# MainSw.net
KiCad netlist of a schematic drawn in Altium Designer
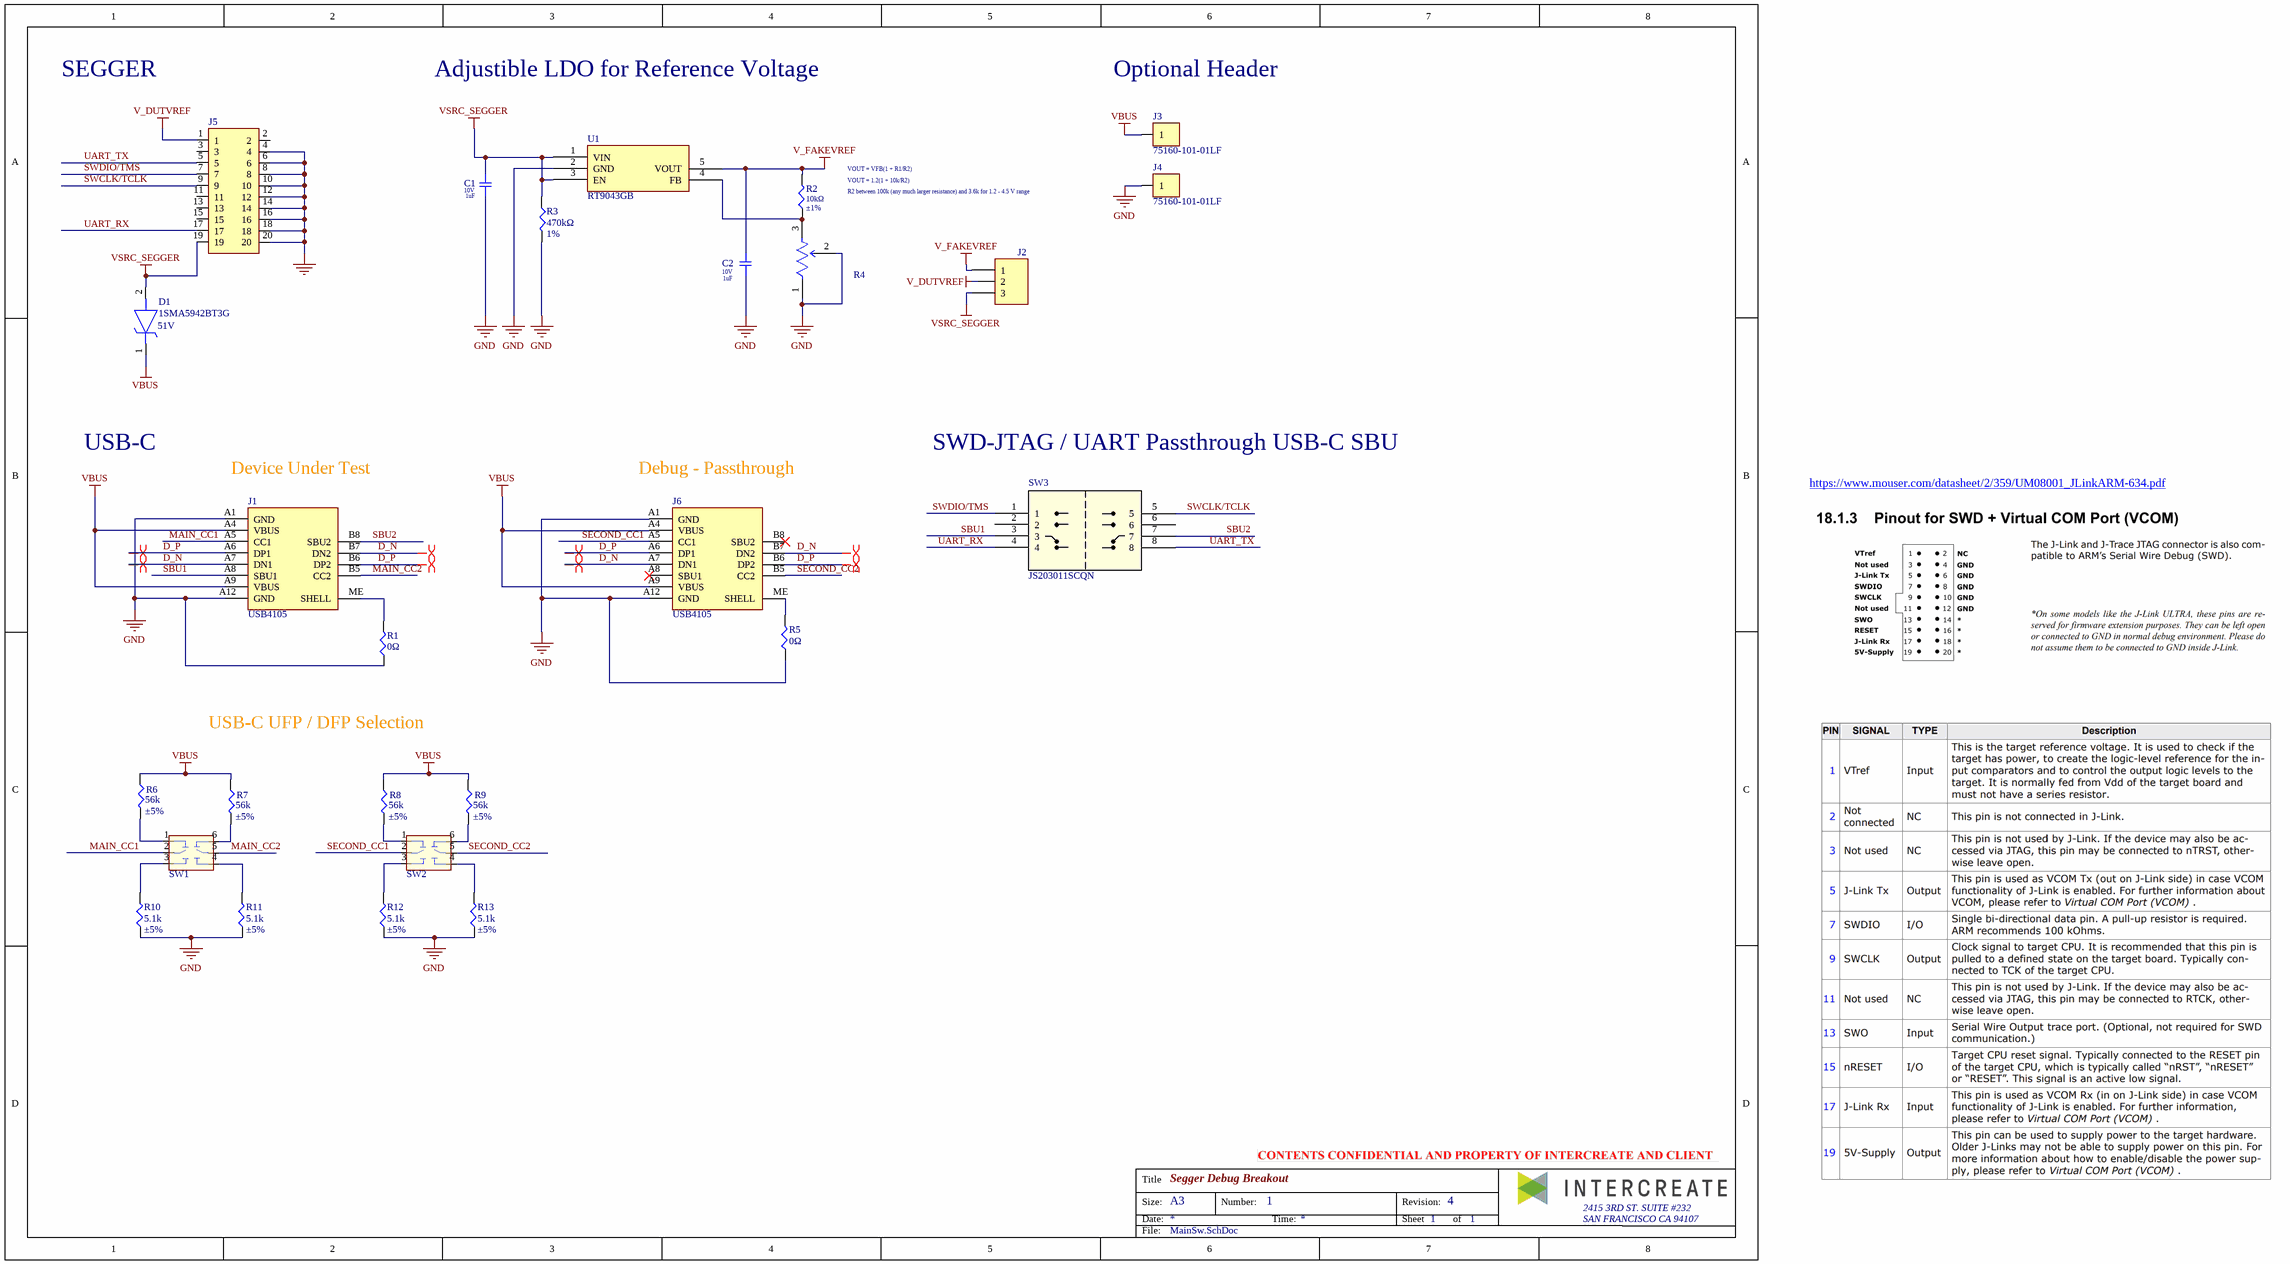
[diagram p0: MainSw.SchDoc]

(export (version "E")
  (design (tool "Eeschema 10.0.6"))
  (components
    (comp (ref "C1")
      (value "0402ZD105KAT2A")
      (footprint "CAP-0402")
      (fields
        (field (name "TOLERANCE") "10%")
        (field (name "VOLTAGE") "10V")
        (field (name "VOLTAGE RATING") "10V")
        (field (name "CAPACITANCE") "1uF")
      )
      (libsource (lib "intercreate") (part "CAP-1uF-10V-0402"))
    )
    (comp (ref "C2")
      (value "0402ZD105KAT2A")
      (footprint "CAP-0402")
      (fields
        (field (name "TOLERANCE") "10%")
        (field (name "VOLTAGE") "10V")
        (field (name "VOLTAGE RATING") "10V")
        (field (name "CAPACITANCE") "1uF")
      )
      (libsource (lib "intercreate") (part "CAP-1uF-10V-0402"))
    )
    (comp (ref "D1")
      (value "1SMA5942BT3G")
      (footprint "DIODE-SMA2")
      (description "Zener Diode 51 V 1.5 W ±5% Surface Mount SMA")
      (fields (field (name "ZENER VOLTAGE") "51V"))
      (libsource (lib "intercreate") (part "DIODE-ZNR-51V-SMA2"))
    )
    (comp (ref "J1")
      (value "USB4105")
      (footprint "CONN-USBC-GCT_USB4105")
      (description "Usb Conn, 2.0 Type C, Rcpt, 16Pos, Smt Rohs Compliant: Yes")
      (libsource (lib "intercreate") (part "CONN-F-USB-C-GCT_USB4105"))
    )
    (comp (ref "J2")
      (value "61300311121")
      (footprint "HDR-V-1X3")
      (description "Header, 3-Pin, 0.1\"")
      (fields (field (name "MANUFACTURER") "Wurth Electronics") (field (name "PUBLISHER") "Altium Limited"))
      (libsource (lib "intercreate") (part "HDR-V-1X3-M"))
    )
    (comp (ref "J3")
      (value "75160-101-01LF")
      (footprint "HDR-V-1X1-M")
      (libsource (lib "intercreate") (part "HDR-V-1X1-M"))
    )
    (comp (ref "J4")
      (value "75160-101-01LF")
      (footprint "HDR-V-1X1-M")
      (libsource (lib "intercreate") (part "HDR-V-1X1-M"))
    )
    (comp (ref "J5")
      (value "SFH11-PBPC-D10-ST-BK")
      (footprint "HDR-V-2X10-F-2.54MM")
      (description "20 Position Header Connector 0.100\" (2.54mm) Through Hole Gold")
      (libsource (lib "intercreate") (part "HDR-V-2X10-F-2.54MM"))
    )
    (comp (ref "J6")
      (value "USB4105")
      (footprint "CONN-USBC-GCT_USB4105")
      (description "Usb Conn, 2.0 Type C, Rcpt, 16Pos, Smt Rohs Compliant: Yes")
      (libsource (lib "intercreate") (part "CONN-F-USB-C-GCT_USB4105"))
    )
    (comp (ref "R1")
      (value "0Ω")
      (footprint "RES-0402")
      (description "RES 0 OHM JUMPER 1/16W 0402")
      (fields
        (field (name "MANUFACTURER") "Yageo")
        (field (name "MANUFACTURER PART NUMBER") "RC0402FR-070RL")
      )
      (libsource (lib "intercreate") (part "RES-0-0402"))
    )
    (comp (ref "R2")
      (value "10kΩ")
      (footprint "RES-0402")
      (description "RES SMD 10K OHM 1% 1/16W 0402")
      (fields (field (name "TOLERANCE") "±1%") (field (name "Comment") "RC0402FR-0710KL"))
      (libsource (lib "intercreate") (part "RES-10K-0402"))
    )
    (comp (ref "R3")
      (value "470kΩ")
      (footprint "RES-0402")
      (description "RES SMD 470K OHM 1% 1/16W 0402")
      (fields
        (field (name "TOLERANCE") "1%")
        (field (name "RESISTANCE TOLERANCE") "1%")
        (field (name "Comment") "RC0402FR-07470KL")
      )
      (libsource (lib "intercreate") (part "RES-470K-0402"))
    )
    (comp (ref "R4")
      (value "POT-ROT-100K-SMD")
      (footprint "3361P-1-104GLF")
      (description "TRIMMER 100K OHM 0.5W GW TOP ADJ")
      (libsource (lib "intercreate") (part "POT-ROT-100K-SMD"))
    )
    (comp (ref "R5")
      (value "0Ω")
      (footprint "RES-0402")
      (description "RES 0 OHM JUMPER 1/16W 0402")
      (fields
        (field (name "MANUFACTURER") "Yageo")
        (field (name "MANUFACTURER PART NUMBER") "RC0402FR-070RL")
      )
      (libsource (lib "intercreate") (part "RES-0-0402"))
    )
    (comp (ref "R6")
      (value "56k")
      (footprint "RES-0402")
      (description "RES SMD 56K OHM 5% 1/10W 0402")
      (fields
        (field (name "MANUFACTURER") "Panasonic")
        (field (name "MANUFACTURER PART NUMBER") "ERJ2GEJ563X")
        (field (name "TOLERANCE") "±5%")
      )
      (libsource (lib "intercreate") (part "RES-56K-0402-5%"))
    )
    (comp (ref "R7")
      (value "56k")
      (footprint "RES-0402")
      (description "RES SMD 56K OHM 5% 1/10W 0402")
      (fields
        (field (name "MANUFACTURER") "Panasonic")
        (field (name "MANUFACTURER PART NUMBER") "ERJ2GEJ563X")
        (field (name "TOLERANCE") "±5%")
      )
      (libsource (lib "intercreate") (part "RES-56K-0402-5%"))
    )
    (comp (ref "R8")
      (value "56k")
      (footprint "RES-0402")
      (description "RES SMD 56K OHM 5% 1/10W 0402")
      (fields
        (field (name "MANUFACTURER") "Panasonic")
        (field (name "MANUFACTURER PART NUMBER") "ERJ2GEJ563X")
        (field (name "TOLERANCE") "±5%")
      )
      (libsource (lib "intercreate") (part "RES-56K-0402-5%"))
    )
    (comp (ref "R9")
      (value "56k")
      (footprint "RES-0402")
      (description "RES SMD 56K OHM 5% 1/10W 0402")
      (fields
        (field (name "MANUFACTURER") "Panasonic")
        (field (name "MANUFACTURER PART NUMBER") "ERJ2GEJ563X")
        (field (name "TOLERANCE") "±5%")
      )
      (libsource (lib "intercreate") (part "RES-56K-0402-5%"))
    )
    (comp (ref "R10")
      (value "5.1k")
      (footprint "RES-0402")
      (description "RES SMD 5.1K OHM 5% 1/10W 0402")
      (fields (field (name "TOLERANCE") "±5%") (field (name "Comment") "ERJ2GEJ512X"))
      (libsource (lib "intercreate") (part "RES-5.1K-0402"))
    )
    (comp (ref "R11")
      (value "5.1k")
      (footprint "RES-0402")
      (description "RES SMD 5.1K OHM 5% 1/10W 0402")
      (fields (field (name "TOLERANCE") "±5%") (field (name "Comment") "ERJ2GEJ512X"))
      (libsource (lib "intercreate") (part "RES-5.1K-0402"))
    )
    (comp (ref "R12")
      (value "5.1k")
      (footprint "RES-0402")
      (description "RES SMD 5.1K OHM 5% 1/10W 0402")
      (fields (field (name "TOLERANCE") "±5%") (field (name "Comment") "ERJ2GEJ512X"))
      (libsource (lib "intercreate") (part "RES-5.1K-0402"))
    )
    (comp (ref "R13")
      (value "5.1k")
      (footprint "RES-0402")
      (description "RES SMD 5.1K OHM 5% 1/10W 0402")
      (fields (field (name "TOLERANCE") "±5%") (field (name "Comment") "ERJ2GEJ512X"))
      (libsource (lib "intercreate") (part "RES-5.1K-0402"))
    )
    (comp (ref "SW1")
      (value "CS-4-22YTA")
      (footprint "SW-BCD-CS-4-22YTA")
      (description "SWITCH ROTARY DIP DPDT 100MA 16V")
      (fields (field (name "MANUFACTURER") "Nidec Copal"))
      (libsource (lib "intercreate") (part "SW-DPDT-3P-ROTARY"))
    )
    (comp (ref "SW2")
      (value "CS-4-22YTA")
      (footprint "SW-BCD-CS-4-22YTA")
      (description "SWITCH ROTARY DIP DPDT 100MA 16V")
      (fields (field (name "MANUFACTURER") "Nidec Copal"))
      (libsource (lib "intercreate") (part "SW-DPDT-3P-ROTARY"))
    )
    (comp (ref "SW3")
      (value "JS203011SCQN")
      (footprint "SW-2P3T-SMD")
      (description "SWITCH SLIDE DP3T 300MA 6V")
      (libsource (lib "jlam") (part "SW-2P3T-SMD"))
    )
    (comp (ref "U1")
      (value "RT9043GB")
      (footprint "SOT-23-5")
      (description "IC REG LINEAR 3.3V 400mA SOT23-5")
      (libsource (lib "intercreate") (part "IC-PWR-LDO-RT9043GB"))
    )
  )
  (nets
    (net (code "1") (name "/D_N") (class "Default")
      (node (ref "J1") (pin "A7") (pinfunction "DN1_A7") (pintype "passive"))
      (node (ref "J1") (pin "B7") (pinfunction "DN2_B7") (pintype "passive"))
      (node (ref "J6") (pin "A7") (pinfunction "DN1_A7") (pintype "passive"))
      (node (ref "J6") (pin "B7") (pinfunction "DN2_B7") (pintype "passive"))
    )
    (net (code "2") (name "/D_P") (class "Default")
      (node (ref "J1") (pin "A6") (pinfunction "DP1_A6") (pintype "passive"))
      (node (ref "J1") (pin "B6") (pinfunction "DP2_B6") (pintype "passive"))
      (node (ref "J6") (pin "A6") (pinfunction "DP1_A6") (pintype "passive"))
      (node (ref "J6") (pin "B6") (pinfunction "DP2_B6") (pintype "passive"))
    )
    (net (code "3") (name "/MAIN_CC1") (class "Default")
      (node (ref "J1") (pin "A5") (pinfunction "CC1_A5") (pintype "passive"))
      (node (ref "SW1") (pin "2") (pinfunction "2_2") (pintype "passive"))
    )
    (net (code "4") (name "/MAIN_CC2") (class "Default")
      (node (ref "J1") (pin "B5") (pinfunction "CC2_B5") (pintype "passive"))
      (node (ref "SW1") (pin "5") (pinfunction "5_5") (pintype "passive"))
    )
    (net (code "5") (name "/SBU1") (class "Default")
      (node (ref "J1") (pin "A8") (pinfunction "SBU1_A8") (pintype "passive"))
      (node (ref "SW3") (pin "3") (pinfunction "3_3") (pintype "passive"))
    )
    (net (code "6") (name "/SBU2") (class "Default")
      (node (ref "J1") (pin "B8") (pinfunction "SBU2_B8") (pintype "passive"))
      (node (ref "SW3") (pin "7") (pinfunction "7_7") (pintype "passive"))
    )
    (net (code "7") (name "/SECOND_CC1") (class "Default")
      (node (ref "J6") (pin "A5") (pinfunction "CC1_A5") (pintype "passive"))
      (node (ref "SW2") (pin "2") (pinfunction "2_2") (pintype "passive"))
    )
    (net (code "8") (name "/SECOND_CC2") (class "Default")
      (node (ref "J6") (pin "B5") (pinfunction "CC2_B5") (pintype "passive"))
      (node (ref "SW2") (pin "5") (pinfunction "5_5") (pintype "passive"))
    )
    (net (code "9") (name "/SWCLK{slash}TCLK") (class "Default")
      (node (ref "J5") (pin "9") (pinfunction "9_9") (pintype "passive"))
      (node (ref "SW3") (pin "5") (pinfunction "5_5") (pintype "passive"))
    )
    (net (code "10") (name "/SWDIO{slash}TMS") (class "Default")
      (node (ref "J5") (pin "7") (pinfunction "7_7") (pintype "passive"))
      (node (ref "SW3") (pin "1") (pinfunction "1_1") (pintype "passive"))
    )
    (net (code "11") (name "/UART_RX") (class "Default")
      (node (ref "J5") (pin "17") (pinfunction "17_17") (pintype "passive"))
      (node (ref "SW3") (pin "4") (pinfunction "4_4") (pintype "passive"))
    )
    (net (code "12") (name "/UART_TX") (class "Default")
      (node (ref "J5") (pin "5") (pinfunction "5_5") (pintype "passive"))
      (node (ref "SW3") (pin "8") (pinfunction "8_8") (pintype "passive"))
    )
    (net (code "13") (name "GND") (class "Default")
      (node (ref "C1") (pin "1") (pinfunction "1_1") (pintype "passive"))
      (node (ref "C2") (pin "1") (pinfunction "1_1") (pintype "passive"))
      (node (ref "J1") (pin "A1") (pinfunction "GND_A1") (pintype "passive"))
      (node (ref "J1") (pin "A12") (pinfunction "GND_A12") (pintype "passive"))
      (node (ref "J4") (pin "1") (pinfunction "1_1") (pintype "passive"))
      (node (ref "J5") (pin "10") (pinfunction "10_10") (pintype "passive"))
      (node (ref "J5") (pin "12") (pinfunction "12_12") (pintype "passive"))
      (node (ref "J5") (pin "14") (pinfunction "14_14") (pintype "passive"))
      (node (ref "J5") (pin "16") (pinfunction "16_16") (pintype "passive"))
      (node (ref "J5") (pin "18") (pinfunction "18_18") (pintype "passive"))
      (node (ref "J5") (pin "20") (pinfunction "20_20") (pintype "passive"))
      (node (ref "J5") (pin "4") (pinfunction "4_4") (pintype "passive"))
      (node (ref "J5") (pin "6") (pinfunction "6_6") (pintype "passive"))
      (node (ref "J5") (pin "8") (pinfunction "8_8") (pintype "passive"))
      (node (ref "J6") (pin "A1") (pinfunction "GND_A1") (pintype "passive"))
      (node (ref "J6") (pin "A12") (pinfunction "GND_A12") (pintype "passive"))
      (node (ref "R1") (pin "1") (pinfunction "1_1") (pintype "passive"))
      (node (ref "R10") (pin "1") (pinfunction "1_1") (pintype "passive"))
      (node (ref "R11") (pin "1") (pinfunction "1_1") (pintype "passive"))
      (node (ref "R12") (pin "1") (pinfunction "1_1") (pintype "passive"))
      (node (ref "R13") (pin "1") (pinfunction "1_1") (pintype "passive"))
      (node (ref "R3") (pin "2") (pinfunction "2_2") (pintype "passive"))
      (node (ref "R4") (pin "1") (pinfunction "CCW_1") (pintype "passive"))
      (node (ref "R4") (pin "2") (pinfunction "WIPER_2") (pintype "passive"))
      (node (ref "R5") (pin "1") (pinfunction "1_1") (pintype "passive"))
      (node (ref "U1") (pin "2") (pinfunction "GND_2") (pintype "passive"))
    )
    (net (code "14") (name "Net-(J1-SHELL)") (class "Default")
      (node (ref "J1") (pin "ME") (pinfunction "SHELL_ME") (pintype "passive"))
      (node (ref "R1") (pin "2") (pinfunction "2_2") (pintype "passive"))
    )
    (net (code "15") (name "Net-(J6-SHELL)") (class "Default")
      (node (ref "J6") (pin "ME") (pinfunction "SHELL_ME") (pintype "passive"))
      (node (ref "R5") (pin "2") (pinfunction "2_2") (pintype "passive"))
    )
    (net (code "16") (name "Net-(R4-CW)") (class "Default")
      (node (ref "R2") (pin "1") (pinfunction "1_1") (pintype "passive"))
      (node (ref "R4") (pin "3") (pinfunction "CW_3") (pintype "passive"))
      (node (ref "U1") (pin "4") (pinfunction "FB_4") (pintype "passive"))
    )
    (net (code "17") (name "Net-(R6-Pad2)") (class "Default")
      (node (ref "R6") (pin "2") (pinfunction "2_2") (pintype "passive"))
      (node (ref "SW1") (pin "1") (pinfunction "1_1") (pintype "passive"))
    )
    (net (code "18") (name "Net-(R7-Pad2)") (class "Default")
      (node (ref "R7") (pin "2") (pinfunction "2_2") (pintype "passive"))
      (node (ref "SW1") (pin "6") (pinfunction "6_6") (pintype "passive"))
    )
    (net (code "19") (name "Net-(R8-Pad2)") (class "Default")
      (node (ref "R8") (pin "2") (pinfunction "2_2") (pintype "passive"))
      (node (ref "SW2") (pin "1") (pinfunction "1_1") (pintype "passive"))
    )
    (net (code "20") (name "Net-(R9-Pad2)") (class "Default")
      (node (ref "R9") (pin "2") (pinfunction "2_2") (pintype "passive"))
      (node (ref "SW2") (pin "6") (pinfunction "6_6") (pintype "passive"))
    )
    (net (code "21") (name "Net-(R10-Pad2)") (class "Default")
      (node (ref "R10") (pin "2") (pinfunction "2_2") (pintype "passive"))
      (node (ref "SW1") (pin "3") (pinfunction "3_3") (pintype "passive"))
    )
    (net (code "22") (name "Net-(R11-Pad2)") (class "Default")
      (node (ref "R11") (pin "2") (pinfunction "2_2") (pintype "passive"))
      (node (ref "SW1") (pin "4") (pinfunction "4_4") (pintype "passive"))
    )
    (net (code "23") (name "Net-(R12-Pad2)") (class "Default")
      (node (ref "R12") (pin "2") (pinfunction "2_2") (pintype "passive"))
      (node (ref "SW2") (pin "3") (pinfunction "3_3") (pintype "passive"))
    )
    (net (code "24") (name "Net-(R13-Pad2)") (class "Default")
      (node (ref "R13") (pin "2") (pinfunction "2_2") (pintype "passive"))
      (node (ref "SW2") (pin "4") (pinfunction "4_4") (pintype "passive"))
    )
    (net (code "25") (name "VBUS") (class "Default")
      (node (ref "D1") (pin "1") (pinfunction "K_1") (pintype "passive"))
      (node (ref "J1") (pin "A4") (pinfunction "VBUS_A4") (pintype "passive"))
      (node (ref "J1") (pin "A9") (pinfunction "VBUS_A9") (pintype "passive"))
      (node (ref "J3") (pin "1") (pinfunction "1_1") (pintype "passive"))
      (node (ref "J6") (pin "A4") (pinfunction "VBUS_A4") (pintype "passive"))
      (node (ref "J6") (pin "A9") (pinfunction "VBUS_A9") (pintype "passive"))
      (node (ref "R6") (pin "1") (pinfunction "1_1") (pintype "passive"))
      (node (ref "R7") (pin "1") (pinfunction "1_1") (pintype "passive"))
      (node (ref "R8") (pin "1") (pinfunction "1_1") (pintype "passive"))
      (node (ref "R9") (pin "1") (pinfunction "1_1") (pintype "passive"))
    )
    (net (code "26") (name "VSRC_SEGGER") (class "Default")
      (node (ref "C1") (pin "2") (pinfunction "2_2") (pintype "passive"))
      (node (ref "D1") (pin "2") (pinfunction "A_2") (pintype "passive"))
      (node (ref "J2") (pin "3") (pinfunction "3_3") (pintype "passive"))
      (node (ref "J5") (pin "19") (pinfunction "19_19") (pintype "passive"))
      (node (ref "R3") (pin "1") (pinfunction "1_1") (pintype "passive"))
      (node (ref "U1") (pin "1") (pinfunction "VIN_1") (pintype "passive"))
      (node (ref "U1") (pin "3") (pinfunction "EN_3") (pintype "passive"))
    )
    (net (code "27") (name "V_DUTVREF") (class "Default")
      (node (ref "J2") (pin "2") (pinfunction "2_2") (pintype "passive"))
      (node (ref "J5") (pin "1") (pinfunction "1_1") (pintype "passive"))
    )
    (net (code "28") (name "V_FAKEVREF") (class "Default")
      (node (ref "C2") (pin "2") (pinfunction "2_2") (pintype "passive"))
      (node (ref "J2") (pin "1") (pinfunction "1_1") (pintype "passive"))
      (node (ref "R2") (pin "2") (pinfunction "2_2") (pintype "passive"))
      (node (ref "U1") (pin "5") (pinfunction "VOUT_5") (pintype "passive"))
    )
    (net (code "29") (name "unconnected-(J5-Pad2)") (class "Default")
      (node (ref "J5") (pin "2") (pinfunction "2_2") (pintype "passive"))
    )
    (net (code "30") (name "unconnected-(J5-Pad3)") (class "Default")
      (node (ref "J5") (pin "3") (pinfunction "3_3") (pintype "passive"))
    )
    (net (code "31") (name "unconnected-(J5-Pad11)") (class "Default")
      (node (ref "J5") (pin "11") (pinfunction "11_11") (pintype "passive"))
    )
    (net (code "32") (name "unconnected-(J5-Pad13)") (class "Default")
      (node (ref "J5") (pin "13") (pinfunction "13_13") (pintype "passive"))
    )
    (net (code "33") (name "unconnected-(J5-Pad15)") (class "Default")
      (node (ref "J5") (pin "15") (pinfunction "15_15") (pintype "passive"))
    )
    (net (code "34") (name "unconnected-(J6-SBU1-PadA8)") (class "Default")
      (node (ref "J6") (pin "A8") (pinfunction "SBU1_A8") (pintype "passive+no_connect"))
    )
    (net (code "35") (name "unconnected-(J6-SBU2-PadB8)") (class "Default")
      (node (ref "J6") (pin "B8") (pinfunction "SBU2_B8") (pintype "passive+no_connect"))
    )
    (net (code "36") (name "unconnected-(SW3-Pad2)") (class "Default")
      (node (ref "SW3") (pin "2") (pinfunction "2_2") (pintype "passive"))
    )
    (net (code "37") (name "unconnected-(SW3-Pad6)") (class "Default")
      (node (ref "SW3") (pin "6") (pinfunction "6_6") (pintype "passive"))
    )
  )
)
